# smartplug.net
KiCad netlist of a schematic drawn in EAGLE
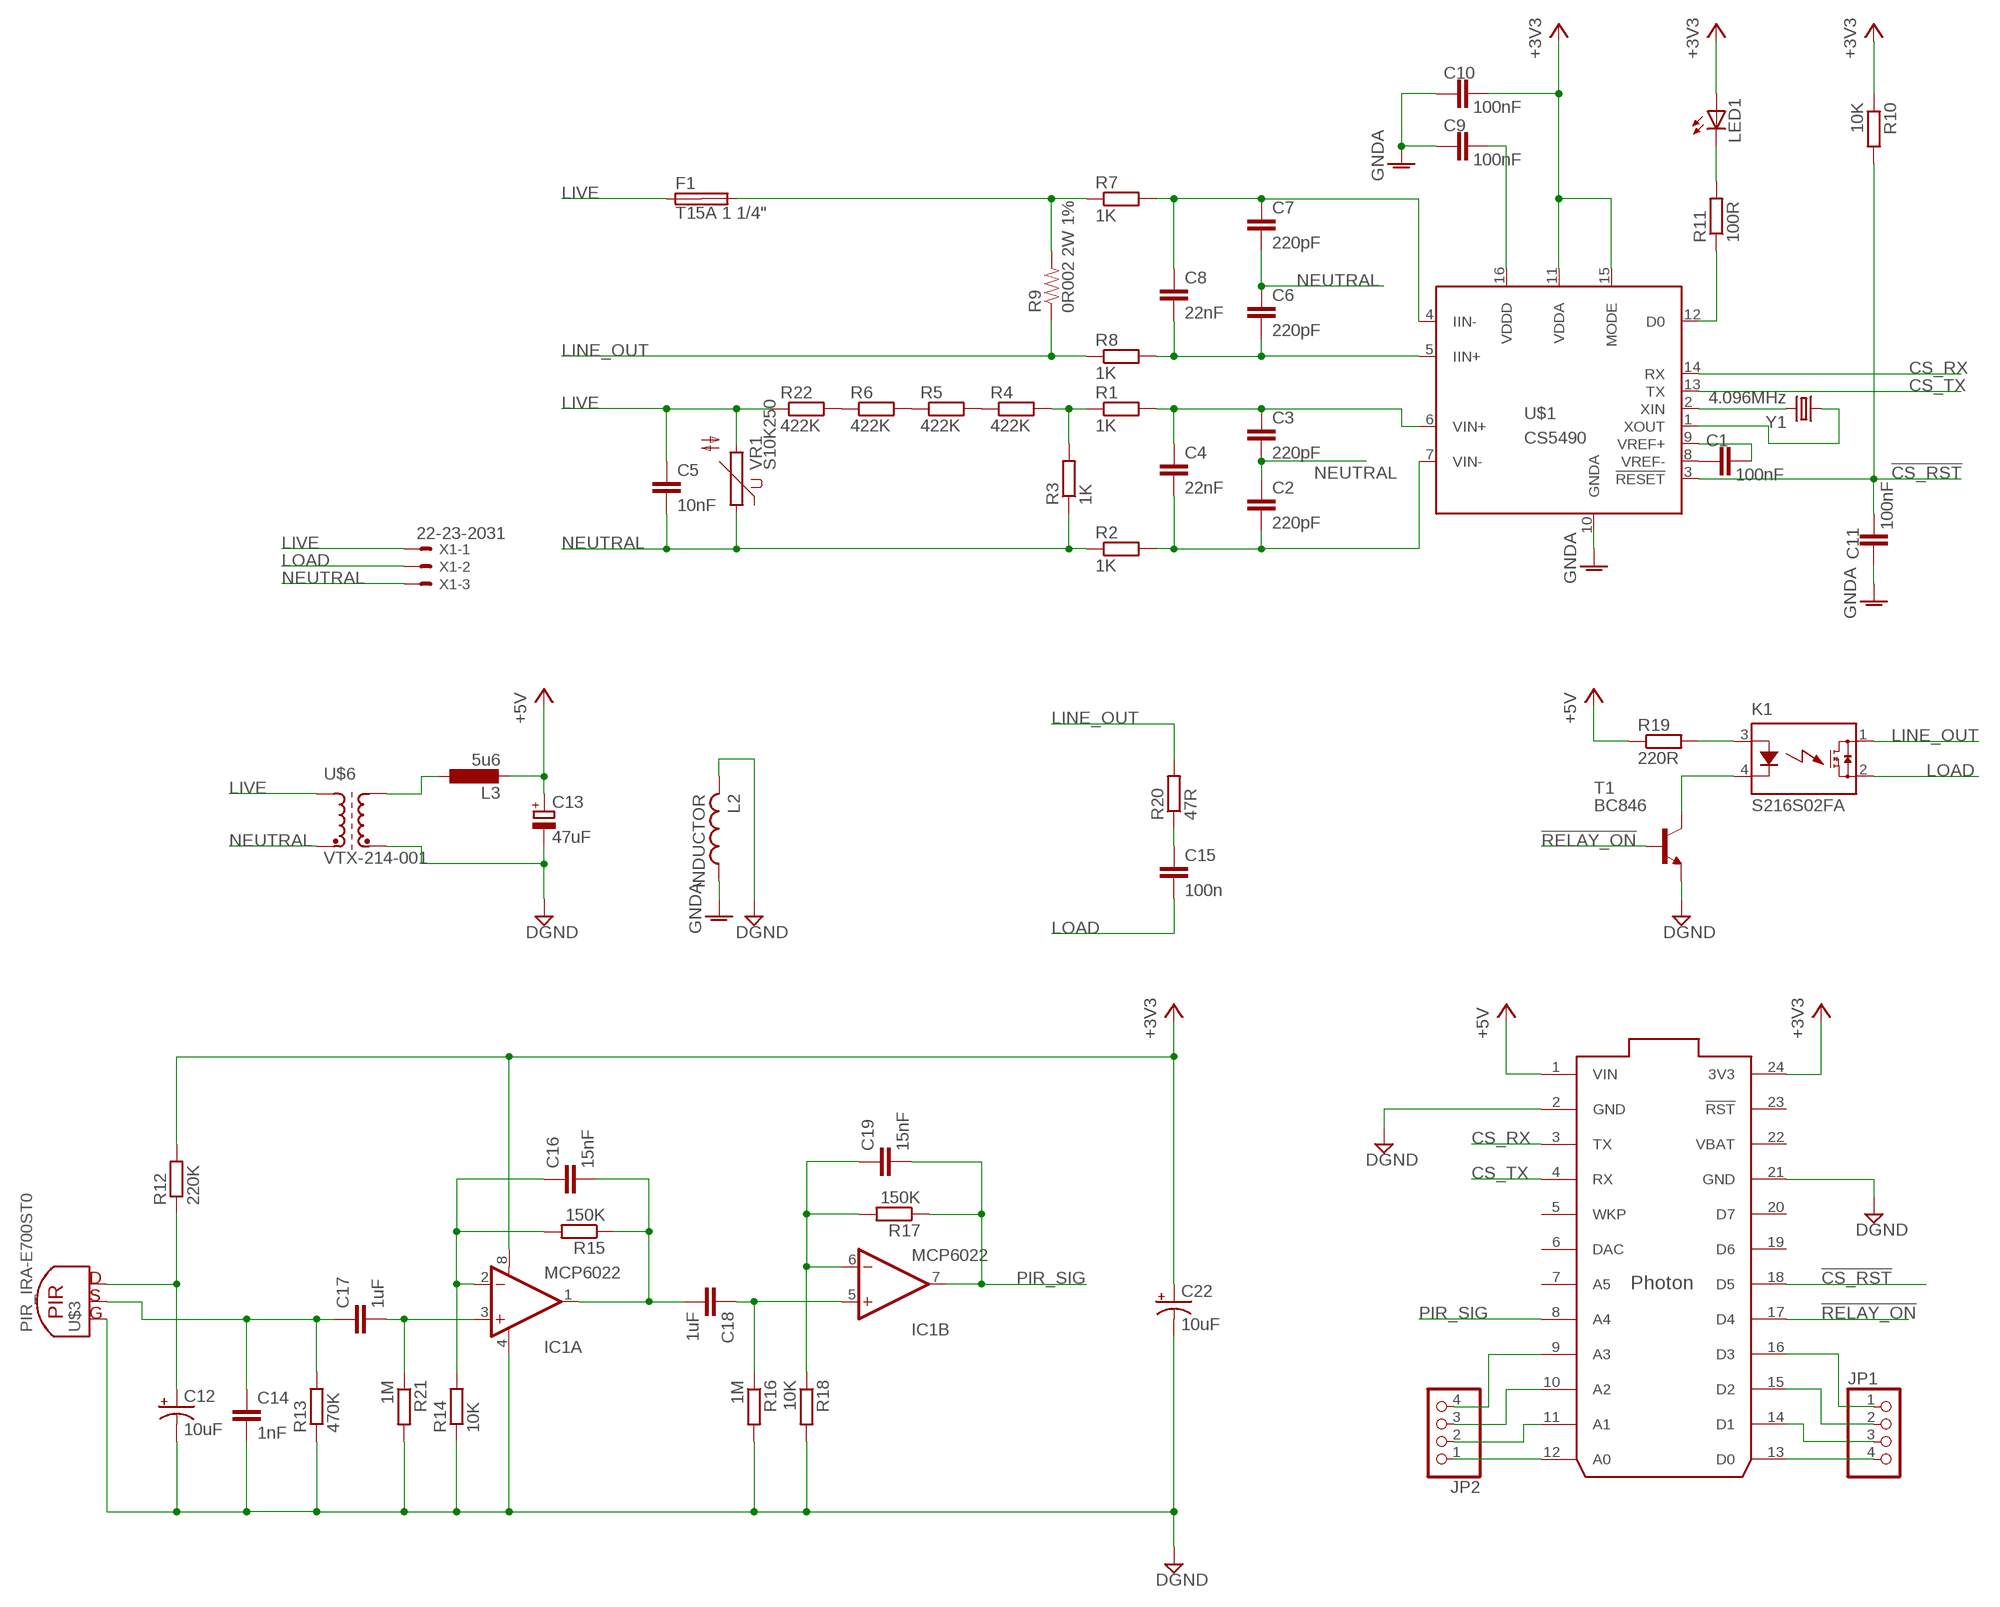
[diagram p0: schematic, sheet 1]

(export (version "E")
  (design (tool "Eeschema 10.0.6"))
  (components
    (comp (ref "C1")
      (value "100nF")
      (footprint "eagle-import:0603-CAP")
      (libsource (lib "eagle-import") (part "CAP0603-CAP"))
    )
    (comp (ref "C2")
      (value "220pF")
      (footprint "eagle-import:0603-CAP")
      (libsource (lib "eagle-import") (part "CAP0603-CAP"))
    )
    (comp (ref "C3")
      (value "220pF")
      (footprint "eagle-import:0603-CAP")
      (libsource (lib "eagle-import") (part "CAP0603-CAP"))
    )
    (comp (ref "C4")
      (value "22nF")
      (footprint "eagle-import:0603-CAP")
      (libsource (lib "eagle-import") (part "CAP0603-CAP"))
    )
    (comp (ref "C5")
      (value "10nF")
      (footprint "eagle-import:0603-CAP")
      (libsource (lib "eagle-import") (part "CAP0603-CAP"))
    )
    (comp (ref "C6")
      (value "220pF")
      (footprint "eagle-import:0603-CAP")
      (libsource (lib "eagle-import") (part "CAP0603-CAP"))
    )
    (comp (ref "C7")
      (value "220pF")
      (footprint "eagle-import:0603-CAP")
      (libsource (lib "eagle-import") (part "CAP0603-CAP"))
    )
    (comp (ref "C8")
      (value "22nF")
      (footprint "eagle-import:0603-CAP")
      (libsource (lib "eagle-import") (part "CAP0603-CAP"))
    )
    (comp (ref "C9")
      (value "100nF")
      (footprint "eagle-import:0603-CAP")
      (libsource (lib "eagle-import") (part "CAP0603-CAP"))
    )
    (comp (ref "C10")
      (value "100nF")
      (footprint "eagle-import:0603-CAP")
      (libsource (lib "eagle-import") (part "CAP0603-CAP"))
    )
    (comp (ref "C11")
      (value "100nF")
      (footprint "eagle-import:0603-CAP")
      (libsource (lib "eagle-import") (part "CAP0603-CAP"))
    )
    (comp (ref "C12")
      (value "10uF")
      (footprint "eagle-import:EIA3216")
      (libsource (lib "eagle-import") (part "CAP_POL1206"))
    )
    (comp (ref "C13")
      (value "47uF")
      (footprint "eagle-import:153CLV-0505")
      (libsource (lib "eagle-import") (part "CPOL-EU153CLV-0505"))
    )
    (comp (ref "C14")
      (value "1nF")
      (footprint "eagle-import:0603-CAP")
      (libsource (lib "eagle-import") (part "smartplug_CAP0603-CAP"))
    )
    (comp (ref "C15")
      (value "100n")
      (footprint "eagle-import:C150-054X183")
      (libsource (lib "eagle-import") (part "C-EU150-054X183"))
    )
    (comp (ref "C16")
      (value "15nF")
      (footprint "eagle-import:0603-CAP")
      (libsource (lib "eagle-import") (part "smartplug_CAP0603-CAP"))
    )
    (comp (ref "C17")
      (value "1uF")
      (footprint "eagle-import:0603-CAP")
      (libsource (lib "eagle-import") (part "smartplug_CAP0603-CAP"))
    )
    (comp (ref "C18")
      (value "1uF")
      (footprint "eagle-import:0603-CAP")
      (libsource (lib "eagle-import") (part "smartplug_CAP0603-CAP"))
    )
    (comp (ref "C19")
      (value "15nF")
      (footprint "eagle-import:0603-CAP")
      (libsource (lib "eagle-import") (part "smartplug_CAP0603-CAP"))
    )
    (comp (ref "C22")
      (value "10uF")
      (footprint "eagle-import:EIA3216")
      (libsource (lib "eagle-import") (part "CAP_POL1206"))
    )
    (comp (ref "F1")
      (value "T15A 1 1/4\"")
      (footprint "eagle-import:SH32")
      (fields (field (name "MPN") "10207101009"))
      (libsource (lib "eagle-import") (part "SH32"))
    )
    (comp (ref "IC1")
      (value "MCP6022")
      (footprint "eagle-import:SO08")
      (libsource (lib "eagle-import") (part "OPAMP-DUALU"))
    )
    (comp (ref "JP1")
      (value "PINHD-1X4")
      (footprint "eagle-import:1X04")
      (libsource (lib "eagle-import") (part "PINHD-1X4"))
    )
    (comp (ref "JP2")
      (value "PINHD-1X4")
      (footprint "eagle-import:1X04")
      (libsource (lib "eagle-import") (part "PINHD-1X4"))
    )
    (comp (ref "K1")
      (value "S216S02FA")
      (footprint "eagle-import:S216S02F")
      (fields (field (name "MANUF_PART#") "S216S02F"))
      (libsource (lib "eagle-import") (part "S216S02FA"))
    )
    (comp (ref "L2")
      (value "INDUCTOR")
      (footprint "eagle-import:0603")
      (libsource (lib "eagle-import") (part "INDUCTOR"))
    )
    (comp (ref "L3")
      (value "5u6")
      (footprint "eagle-import:ELLCTP")
      (libsource (lib "eagle-import") (part "ELLCTP"))
    )
    (comp (ref "LED1")
      (value "LEDCHIPLED_1206")
      (footprint "eagle-import:CHIPLED_1206")
      (libsource (lib "eagle-import") (part "LEDCHIPLED_1206"))
    )
    (comp (ref "R1")
      (value "1K")
      (footprint "eagle-import:0603")
      (libsource (lib "eagle-import") (part "R-EU_0603"))
    )
    (comp (ref "R2")
      (value "1K")
      (footprint "eagle-import:0603")
      (libsource (lib "eagle-import") (part "R-EU_0603"))
    )
    (comp (ref "R3")
      (value "1K")
      (footprint "eagle-import:0603")
      (libsource (lib "eagle-import") (part "R-EU_0603"))
    )
    (comp (ref "R4")
      (value "422K")
      (footprint "eagle-import:0603")
      (libsource (lib "eagle-import") (part "R-EU_0603"))
    )
    (comp (ref "R5")
      (value "422K")
      (footprint "eagle-import:0603")
      (libsource (lib "eagle-import") (part "R-EU_0603"))
    )
    (comp (ref "R6")
      (value "422K")
      (footprint "eagle-import:0603")
      (libsource (lib "eagle-import") (part "R-EU_0603"))
    )
    (comp (ref "R7")
      (value "1K")
      (footprint "eagle-import:0603")
      (libsource (lib "eagle-import") (part "R-EU_0603"))
    )
    (comp (ref "R8")
      (value "1K")
      (footprint "eagle-import:0603")
      (libsource (lib "eagle-import") (part "R-EU_0603"))
    )
    (comp (ref "R9")
      (value "0R002 2W 1%")
      (footprint "eagle-import:R2512")
      (fields (field (name "MANUF_PART#") "CRF2512-FV-R002ELF"))
      (libsource (lib "eagle-import") (part "RESISTOR2512"))
    )
    (comp (ref "R10")
      (value "10K")
      (footprint "eagle-import:0603")
      (libsource (lib "eagle-import") (part "R-EU_0603"))
    )
    (comp (ref "R11")
      (value "100R")
      (footprint "eagle-import:0603")
      (libsource (lib "eagle-import") (part "R-EU_0603"))
    )
    (comp (ref "R12")
      (value "220K")
      (footprint "eagle-import:0603")
      (libsource (lib "eagle-import") (part "R-EU_0603"))
    )
    (comp (ref "R13")
      (value "470K")
      (footprint "eagle-import:0603")
      (libsource (lib "eagle-import") (part "R-EU_0603"))
    )
    (comp (ref "R14")
      (value "10K")
      (footprint "eagle-import:0603")
      (libsource (lib "eagle-import") (part "R-EU_0603"))
    )
    (comp (ref "R15")
      (value "150K")
      (footprint "eagle-import:0603")
      (libsource (lib "eagle-import") (part "R-EU_0603"))
    )
    (comp (ref "R16")
      (value "1M")
      (footprint "eagle-import:0603")
      (libsource (lib "eagle-import") (part "R-EU_0603"))
    )
    (comp (ref "R17")
      (value "150K")
      (footprint "eagle-import:0603")
      (libsource (lib "eagle-import") (part "R-EU_0603"))
    )
    (comp (ref "R18")
      (value "10K")
      (footprint "eagle-import:0603")
      (libsource (lib "eagle-import") (part "R-EU_0603"))
    )
    (comp (ref "R19")
      (value "220R")
      (footprint "eagle-import:0603")
      (libsource (lib "eagle-import") (part "R-EU_0603"))
    )
    (comp (ref "R20")
      (value "47R")
      (footprint "eagle-import:0617V")
      (libsource (lib "eagle-import") (part "R-EU_0617/5V"))
    )
    (comp (ref "R21")
      (value "1M")
      (footprint "eagle-import:0603")
      (libsource (lib "eagle-import") (part "R-EU_0603"))
    )
    (comp (ref "R22")
      (value "422K")
      (footprint "eagle-import:0603")
      (libsource (lib "eagle-import") (part "R-EU_0603"))
    )
    (comp (ref "T1")
      (value "BC846")
      (footprint "eagle-import:SOT23")
      (libsource (lib "eagle-import") (part "BC846"))
    )
    (comp (ref "U$1")
      (value "CS5490")
      (footprint "eagle-import:SOIC16N")
      (fields (field (name "MANUF_PART#") "CS5490-ISZR"))
      (libsource (lib "eagle-import") (part "CS5490"))
    )
    (comp (ref "U$2")
      (value "PHOTON_WITH_HEADERS")
      (footprint "eagle-import:PHOTON")
      (libsource (lib "eagle-import") (part "PHOTON_WITH_HEADERS"))
    )
    (comp (ref "U$3")
      (value "PIR_IRA-E700ST0")
      (footprint "eagle-import:PIR_IRA-E700ST0")
      (libsource (lib "eagle-import") (part "PIR_IRA-E700ST0"))
    )
    (comp (ref "U$6")
      (value "VTX-214-001")
      (footprint "eagle-import:VTX-214-001")
      (libsource (lib "eagle-import") (part "VTX-214-001"))
    )
    (comp (ref "VR1")
      (value "S10K250")
      (footprint "eagle-import:S10K250")
      (fields (field (name "MANUF_PART#") "B72210S0251K101"))
      (libsource (lib "eagle-import") (part "S10K250"))
    )
    (comp (ref "X1")
      (value "22-23-2031")
      (footprint "eagle-import:22-23-2031")
      (fields (field (name "MF") "MOLEX"))
      (libsource (lib "eagle-import") (part "22-23-2031"))
    )
    (comp (ref "Y1")
      (value "4.096MHz")
      (footprint "eagle-import:CRYSTAL-SMD-10.5X4.8-2PIN")
      (fields (field (name "MANUF_PART#") "ABLS2-4.096MHZ-D4Y-T"))
      (libsource (lib "eagle-import") (part "CRYSTAL10.5X4.8"))
    )
  )
  (nets
    (net (code "1") (name "+3V3") (class "Default")
      (node (ref "C10") (pin "2") (pinfunction "2_2") (pintype "passive"))
      (node (ref "C22") (pin "A") (pinfunction "+_A") (pintype "passive"))
      (node (ref "IC1") (pin "8") (pinfunction "V+_8") (pintype "power_in"))
      (node (ref "LED1") (pin "A") (pinfunction "A_A") (pintype "passive"))
      (node (ref "R10") (pin "1") (pinfunction "1_1") (pintype "passive"))
      (node (ref "R12") (pin "2") (pinfunction "2_2") (pintype "passive"))
      (node (ref "U$1") (pin "11") (pinfunction "VDDA_11") (pintype "input"))
      (node (ref "U$1") (pin "15") (pinfunction "MODE_15") (pintype "input"))
      (node (ref "U$2") (pin "24") (pinfunction "3V3_24") (pintype "power_in"))
    )
    (net (code "2") (name "+5V") (class "Default")
      (node (ref "C13") (pin "+") (pinfunction "+_+") (pintype "passive"))
      (node (ref "L3") (pin "2") (pinfunction "2_2") (pintype "passive"))
      (node (ref "R19") (pin "1") (pinfunction "1_1") (pintype "passive"))
      (node (ref "U$2") (pin "1") (pinfunction "VIN_1") (pintype "power_in"))
    )
    (net (code "3") (name "/CS_RX") (class "Default")
      (node (ref "U$1") (pin "14") (pinfunction "RX_14") (pintype "input"))
      (node (ref "U$2") (pin "3") (pinfunction "TX_3") (pintype "bidirectional"))
    )
    (net (code "4") (name "/CS_TX") (class "Default")
      (node (ref "U$1") (pin "13") (pinfunction "TX_13") (pintype "output"))
      (node (ref "U$2") (pin "4") (pinfunction "RX_4") (pintype "bidirectional"))
    )
    (net (code "5") (name "/LINE_OUT") (class "Default")
      (node (ref "K1") (pin "1") (pinfunction "DS1_1") (pintype "passive"))
      (node (ref "R20") (pin "2") (pinfunction "2_2") (pintype "passive"))
      (node (ref "R8") (pin "1") (pinfunction "1_1") (pintype "passive"))
      (node (ref "R9") (pin "1") (pinfunction "1_1") (pintype "passive"))
    )
    (net (code "6") (name "/LIVE") (class "Default")
      (node (ref "C5") (pin "1") (pinfunction "1_1") (pintype "passive"))
      (node (ref "F1") (pin "1A") (pinfunction "1A_1A") (pintype "passive"))
      (node (ref "R22") (pin "1") (pinfunction "1_1") (pintype "passive"))
      (node (ref "U$6") (pin "P$L") (pinfunction "A1_P$L") (pintype "passive"))
      (node (ref "VR1") (pin "2") (pinfunction "2_2") (pintype "passive"))
      (node (ref "X1") (pin "1") (pinfunction "S_1") (pintype "passive"))
    )
    (net (code "7") (name "/LOAD") (class "Default")
      (node (ref "C15") (pin "2") (pinfunction "2_2") (pintype "passive"))
      (node (ref "K1") (pin "2") (pinfunction "DS2_2") (pintype "passive"))
      (node (ref "X1") (pin "2") (pinfunction "S_2") (pintype "passive"))
    )
    (net (code "8") (name "/NEUTRAL") (class "Default")
      (node (ref "C2") (pin "1") (pinfunction "1_1") (pintype "passive"))
      (node (ref "C3") (pin "2") (pinfunction "2_2") (pintype "passive"))
      (node (ref "C5") (pin "2") (pinfunction "2_2") (pintype "passive"))
      (node (ref "C6") (pin "1") (pinfunction "1_1") (pintype "passive"))
      (node (ref "C7") (pin "2") (pinfunction "2_2") (pintype "passive"))
      (node (ref "R2") (pin "1") (pinfunction "1_1") (pintype "passive"))
      (node (ref "R3") (pin "1") (pinfunction "1_1") (pintype "passive"))
      (node (ref "U$6") (pin "P$N") (pinfunction "E1_P$N") (pintype "passive"))
      (node (ref "VR1") (pin "1") (pinfunction "1_1") (pintype "passive"))
      (node (ref "X1") (pin "3") (pinfunction "S_3") (pintype "passive"))
    )
    (net (code "9") (name "/PIR_SIG") (class "Default")
      (node (ref "C19") (pin "2") (pinfunction "2_2") (pintype "passive"))
      (node (ref "IC1") (pin "7") (pinfunction "OUT_7") (pintype "output"))
      (node (ref "R17") (pin "1") (pinfunction "1_1") (pintype "passive"))
      (node (ref "U$2") (pin "8") (pinfunction "A4_8") (pintype "bidirectional"))
    )
    (net (code "10") (name "/VBAT") (class "Default")
      (node (ref "U$2") (pin "22") (pinfunction "VBAT_22") (pintype "power_in"))
    )
    (net (code "11") (name "/~{CS_RST}") (class "Default")
      (node (ref "C11") (pin "2") (pinfunction "2_2") (pintype "passive"))
      (node (ref "R10") (pin "2") (pinfunction "2_2") (pintype "passive"))
      (node (ref "U$1") (pin "3") (pinfunction "~{RESET}_3") (pintype "input"))
      (node (ref "U$2") (pin "18") (pinfunction "D5_18") (pintype "bidirectional"))
    )
    (net (code "12") (name "/~{RELAY_ON}") (class "Default")
      (node (ref "T1") (pin "1") (pinfunction "B_1") (pintype "passive"))
      (node (ref "U$2") (pin "17") (pinfunction "D4_17") (pintype "bidirectional"))
    )
    (net (code "13") (name "DGND") (class "Default")
      (node (ref "C12") (pin "C") (pinfunction "-_C") (pintype "passive"))
      (node (ref "C13") (pin "-") (pinfunction "-_-") (pintype "passive"))
      (node (ref "C14") (pin "2") (pinfunction "2_2") (pintype "passive"))
      (node (ref "C22") (pin "C") (pinfunction "-_C") (pintype "passive"))
      (node (ref "IC1") (pin "4") (pinfunction "V-_4") (pintype "power_in"))
      (node (ref "L2") (pin "2") (pinfunction "2_2") (pintype "passive"))
      (node (ref "R13") (pin "1") (pinfunction "1_1") (pintype "passive"))
      (node (ref "R14") (pin "1") (pinfunction "1_1") (pintype "passive"))
      (node (ref "R16") (pin "2") (pinfunction "2_2") (pintype "passive"))
      (node (ref "R18") (pin "2") (pinfunction "2_2") (pintype "passive"))
      (node (ref "R21") (pin "2") (pinfunction "2_2") (pintype "passive"))
      (node (ref "T1") (pin "2") (pinfunction "E_2") (pintype "passive"))
      (node (ref "U$2") (pin "2") (pinfunction "GND_2") (pintype "power_in"))
      (node (ref "U$2") (pin "21") (pinfunction "GND_21") (pintype "power_in"))
      (node (ref "U$3") (pin "GND") (pinfunction "GND_GND") (pintype "power_in"))
      (node (ref "U$6") (pin "P$V-") (pinfunction "E2_P$V-") (pintype "passive"))
    )
    (net (code "14") (name "GNDA") (class "Default")
      (node (ref "C10") (pin "1") (pinfunction "1_1") (pintype "passive"))
      (node (ref "C11") (pin "1") (pinfunction "1_1") (pintype "passive"))
      (node (ref "C9") (pin "1") (pinfunction "1_1") (pintype "passive"))
      (node (ref "L2") (pin "1") (pinfunction "1_1") (pintype "passive"))
      (node (ref "U$1") (pin "10") (pinfunction "GNDA_10") (pintype "power_in"))
    )
    (net (code "15") (name "Net-(C12-+)") (class "Default")
      (node (ref "C12") (pin "A") (pinfunction "+_A") (pintype "passive"))
      (node (ref "R12") (pin "1") (pinfunction "1_1") (pintype "passive"))
      (node (ref "U$3") (pin "DRAIN+") (pinfunction "DRAIN_DRAIN+") (pintype "passive"))
    )
    (net (code "16") (name "Net-(C14-Pad1)") (class "Default")
      (node (ref "C14") (pin "1") (pinfunction "1_1") (pintype "passive"))
      (node (ref "C17") (pin "1") (pinfunction "1_1") (pintype "passive"))
      (node (ref "R13") (pin "2") (pinfunction "2_2") (pintype "passive"))
      (node (ref "U$3") (pin "SOURCE") (pinfunction "SOURCE_SOURCE") (pintype "output"))
    )
    (net (code "17") (name "Net-(C15-Pad1)") (class "Default")
      (node (ref "C15") (pin "1") (pinfunction "1_1") (pintype "passive"))
      (node (ref "R20") (pin "1") (pinfunction "1_1") (pintype "passive"))
    )
    (net (code "18") (name "Net-(F1-Pad2A)") (class "Default")
      (node (ref "F1") (pin "2A") (pinfunction "2A_2A") (pintype "passive"))
      (node (ref "R7") (pin "1") (pinfunction "1_1") (pintype "passive"))
      (node (ref "R9") (pin "2") (pinfunction "2_2") (pintype "passive"))
    )
    (net (code "19") (name "Net-(IC1A-+IN)") (class "Default")
      (node (ref "C17") (pin "2") (pinfunction "2_2") (pintype "passive"))
      (node (ref "IC1") (pin "3") (pinfunction "+IN_3") (pintype "input"))
      (node (ref "R21") (pin "1") (pinfunction "1_1") (pintype "passive"))
    )
    (net (code "20") (name "Net-(IC1A--IN)") (class "Default")
      (node (ref "C16") (pin "1") (pinfunction "1_1") (pintype "passive"))
      (node (ref "IC1") (pin "2") (pinfunction "-IN_2") (pintype "input"))
      (node (ref "R14") (pin "2") (pinfunction "2_2") (pintype "passive"))
      (node (ref "R15") (pin "2") (pinfunction "2_2") (pintype "passive"))
    )
    (net (code "21") (name "Net-(IC1A-OUT)") (class "Default")
      (node (ref "C16") (pin "2") (pinfunction "2_2") (pintype "passive"))
      (node (ref "C18") (pin "2") (pinfunction "2_2") (pintype "passive"))
      (node (ref "IC1") (pin "1") (pinfunction "OUT_1") (pintype "output"))
      (node (ref "R15") (pin "1") (pinfunction "1_1") (pintype "passive"))
    )
    (net (code "22") (name "Net-(IC1B-+IN)") (class "Default")
      (node (ref "C18") (pin "1") (pinfunction "1_1") (pintype "passive"))
      (node (ref "IC1") (pin "5") (pinfunction "+IN_5") (pintype "input"))
      (node (ref "R16") (pin "1") (pinfunction "1_1") (pintype "passive"))
    )
    (net (code "23") (name "Net-(IC1B--IN)") (class "Default")
      (node (ref "C19") (pin "1") (pinfunction "1_1") (pintype "passive"))
      (node (ref "IC1") (pin "6") (pinfunction "-IN_6") (pintype "input"))
      (node (ref "R17") (pin "2") (pinfunction "2_2") (pintype "passive"))
      (node (ref "R18") (pin "1") (pinfunction "1_1") (pintype "passive"))
    )
    (net (code "24") (name "Net-(K1-A)") (class "Default")
      (node (ref "K1") (pin "3") (pinfunction "A_3") (pintype "passive"))
      (node (ref "R19") (pin "2") (pinfunction "2_2") (pintype "passive"))
    )
    (net (code "25") (name "Net-(K1-K)") (class "Default")
      (node (ref "K1") (pin "4") (pinfunction "K_4") (pintype "passive"))
      (node (ref "T1") (pin "3") (pinfunction "C_3") (pintype "passive"))
    )
    (net (code "26") (name "Net-(LED1-PadC)") (class "Default")
      (node (ref "LED1") (pin "C") (pinfunction "C_C") (pintype "passive"))
      (node (ref "R11") (pin "2") (pinfunction "2_2") (pintype "passive"))
    )
    (net (code "27") (name "Net-(R1-Pad1)") (class "Default")
      (node (ref "R1") (pin "1") (pinfunction "1_1") (pintype "passive"))
      (node (ref "R3") (pin "2") (pinfunction "2_2") (pintype "passive"))
      (node (ref "R4") (pin "2") (pinfunction "2_2") (pintype "passive"))
    )
    (net (code "28") (name "Net-(R4-Pad1)") (class "Default")
      (node (ref "R4") (pin "1") (pinfunction "1_1") (pintype "passive"))
      (node (ref "R5") (pin "2") (pinfunction "2_2") (pintype "passive"))
    )
    (net (code "29") (name "Net-(R5-Pad1)") (class "Default")
      (node (ref "R5") (pin "1") (pinfunction "1_1") (pintype "passive"))
      (node (ref "R6") (pin "2") (pinfunction "2_2") (pintype "passive"))
    )
    (net (code "30") (name "Net-(R22-Pad2)") (class "Default")
      (node (ref "R22") (pin "2") (pinfunction "2_2") (pintype "passive"))
      (node (ref "R6") (pin "1") (pinfunction "1_1") (pintype "passive"))
    )
    (net (code "31") (name "Net-(U$1-D0)") (class "Default")
      (node (ref "R11") (pin "1") (pinfunction "1_1") (pintype "passive"))
      (node (ref "U$1") (pin "12") (pinfunction "D0_12") (pintype "output"))
    )
    (net (code "32") (name "Net-(U$1-IIN+)") (class "Default")
      (node (ref "C6") (pin "2") (pinfunction "2_2") (pintype "passive"))
      (node (ref "C8") (pin "2") (pinfunction "2_2") (pintype "passive"))
      (node (ref "R8") (pin "2") (pinfunction "2_2") (pintype "passive"))
      (node (ref "U$1") (pin "5") (pinfunction "IIN+_5") (pintype "input"))
    )
    (net (code "33") (name "Net-(U$1-IIN-)") (class "Default")
      (node (ref "C7") (pin "1") (pinfunction "1_1") (pintype "passive"))
      (node (ref "C8") (pin "1") (pinfunction "1_1") (pintype "passive"))
      (node (ref "R7") (pin "2") (pinfunction "2_2") (pintype "passive"))
      (node (ref "U$1") (pin "4") (pinfunction "IIN-_4") (pintype "input"))
    )
    (net (code "34") (name "Net-(U$1-VDDD)") (class "Default")
      (node (ref "C9") (pin "2") (pinfunction "2_2") (pintype "passive"))
      (node (ref "U$1") (pin "16") (pinfunction "VDDD_16") (pintype "power_in"))
    )
    (net (code "35") (name "Net-(U$1-VIN+)") (class "Default")
      (node (ref "C3") (pin "1") (pinfunction "1_1") (pintype "passive"))
      (node (ref "C4") (pin "1") (pinfunction "1_1") (pintype "passive"))
      (node (ref "R1") (pin "2") (pinfunction "2_2") (pintype "passive"))
      (node (ref "U$1") (pin "6") (pinfunction "VIN+_6") (pintype "input"))
    )
    (net (code "36") (name "Net-(U$1-VIN-)") (class "Default")
      (node (ref "C2") (pin "2") (pinfunction "2_2") (pintype "passive"))
      (node (ref "C4") (pin "2") (pinfunction "2_2") (pintype "passive"))
      (node (ref "R2") (pin "2") (pinfunction "2_2") (pintype "passive"))
      (node (ref "U$1") (pin "7") (pinfunction "VIN-_7") (pintype "input"))
    )
    (net (code "37") (name "Net-(U$1-VREF+)") (class "Default")
      (node (ref "C1") (pin "2") (pinfunction "2_2") (pintype "passive"))
      (node (ref "U$1") (pin "9") (pinfunction "VREF+_9") (pintype "output"))
    )
    (net (code "38") (name "Net-(U$1-VREF-)") (class "Default")
      (node (ref "C1") (pin "1") (pinfunction "1_1") (pintype "passive"))
      (node (ref "U$1") (pin "8") (pinfunction "VREF-_8") (pintype "input"))
    )
    (net (code "39") (name "Net-(U$1-XIN)") (class "Default")
      (node (ref "U$1") (pin "2") (pinfunction "XIN_2") (pintype "input"))
      (node (ref "Y1") (pin "P$2") (pinfunction "2_P$2") (pintype "passive"))
    )
    (net (code "40") (name "Net-(U$1-XOUT)") (class "Default")
      (node (ref "U$1") (pin "1") (pinfunction "XOUT_1") (pintype "output"))
      (node (ref "Y1") (pin "P$1") (pinfunction "1_P$1") (pintype "passive"))
    )
    (net (code "41") (name "Net-(U$2-A0)") (class "Default")
      (node (ref "JP2") (pin "1") (pinfunction "1_1") (pintype "passive"))
      (node (ref "U$2") (pin "12") (pinfunction "A0_12") (pintype "bidirectional"))
    )
    (net (code "42") (name "Net-(U$2-A1)") (class "Default")
      (node (ref "JP2") (pin "2") (pinfunction "2_2") (pintype "passive"))
      (node (ref "U$2") (pin "11") (pinfunction "A1_11") (pintype "bidirectional"))
    )
    (net (code "43") (name "Net-(U$2-A2)") (class "Default")
      (node (ref "JP2") (pin "3") (pinfunction "3_3") (pintype "passive"))
      (node (ref "U$2") (pin "10") (pinfunction "A2_10") (pintype "bidirectional"))
    )
    (net (code "44") (name "Net-(U$2-A3)") (class "Default")
      (node (ref "JP2") (pin "4") (pinfunction "4_4") (pintype "passive"))
      (node (ref "U$2") (pin "9") (pinfunction "A3_9") (pintype "bidirectional"))
    )
    (net (code "45") (name "Net-(U$2-D0)") (class "Default")
      (node (ref "JP1") (pin "4") (pinfunction "4_4") (pintype "passive"))
      (node (ref "U$2") (pin "13") (pinfunction "D0_13") (pintype "bidirectional"))
    )
    (net (code "46") (name "Net-(U$2-D1)") (class "Default")
      (node (ref "JP1") (pin "3") (pinfunction "3_3") (pintype "passive"))
      (node (ref "U$2") (pin "14") (pinfunction "D1_14") (pintype "bidirectional"))
    )
    (net (code "47") (name "Net-(U$2-D2)") (class "Default")
      (node (ref "JP1") (pin "2") (pinfunction "2_2") (pintype "passive"))
      (node (ref "U$2") (pin "15") (pinfunction "D2_15") (pintype "bidirectional"))
    )
    (net (code "48") (name "Net-(U$2-D3)") (class "Default")
      (node (ref "JP1") (pin "1") (pinfunction "1_1") (pintype "passive"))
      (node (ref "U$2") (pin "16") (pinfunction "D3_16") (pintype "bidirectional"))
    )
    (net (code "49") (name "Net-(U$6-A2)") (class "Default")
      (node (ref "L3") (pin "1") (pinfunction "1_1") (pintype "passive"))
      (node (ref "U$6") (pin "P$V+") (pinfunction "A2_P$V+") (pintype "passive"))
    )
    (net (code "50") (name "unconnected-(F1-Pad1B)") (class "Default")
      (node (ref "F1") (pin "1B") (pinfunction "1B_1B") (pintype "passive"))
    )
    (net (code "51") (name "unconnected-(F1-Pad2B)") (class "Default")
      (node (ref "F1") (pin "2B") (pinfunction "2B_2B") (pintype "passive"))
    )
    (net (code "52") (name "unconnected-(U$2-A5-Pad7)") (class "Default")
      (node (ref "U$2") (pin "7") (pinfunction "A5_7") (pintype "bidirectional"))
    )
    (net (code "53") (name "unconnected-(U$2-D6-Pad19)") (class "Default")
      (node (ref "U$2") (pin "19") (pinfunction "D6_19") (pintype "bidirectional"))
    )
    (net (code "54") (name "unconnected-(U$2-D7-Pad20)") (class "Default")
      (node (ref "U$2") (pin "20") (pinfunction "D7_20") (pintype "bidirectional"))
    )
    (net (code "55") (name "unconnected-(U$2-DAC-Pad6)") (class "Default")
      (node (ref "U$2") (pin "6") (pinfunction "DAC_6") (pintype "bidirectional"))
    )
    (net (code "56") (name "unconnected-(U$2-WKP-Pad5)") (class "Default")
      (node (ref "U$2") (pin "5") (pinfunction "WKP_5") (pintype "bidirectional"))
    )
    (net (code "57") (name "unconnected-(U$2-~{RST}-Pad23)") (class "Default")
      (node (ref "U$2") (pin "23") (pinfunction "~{RST}_23") (pintype "bidirectional"))
    )
  )
)
